# E_Key_BT.net
KiCad netlist of a schematic drawn in EAGLE
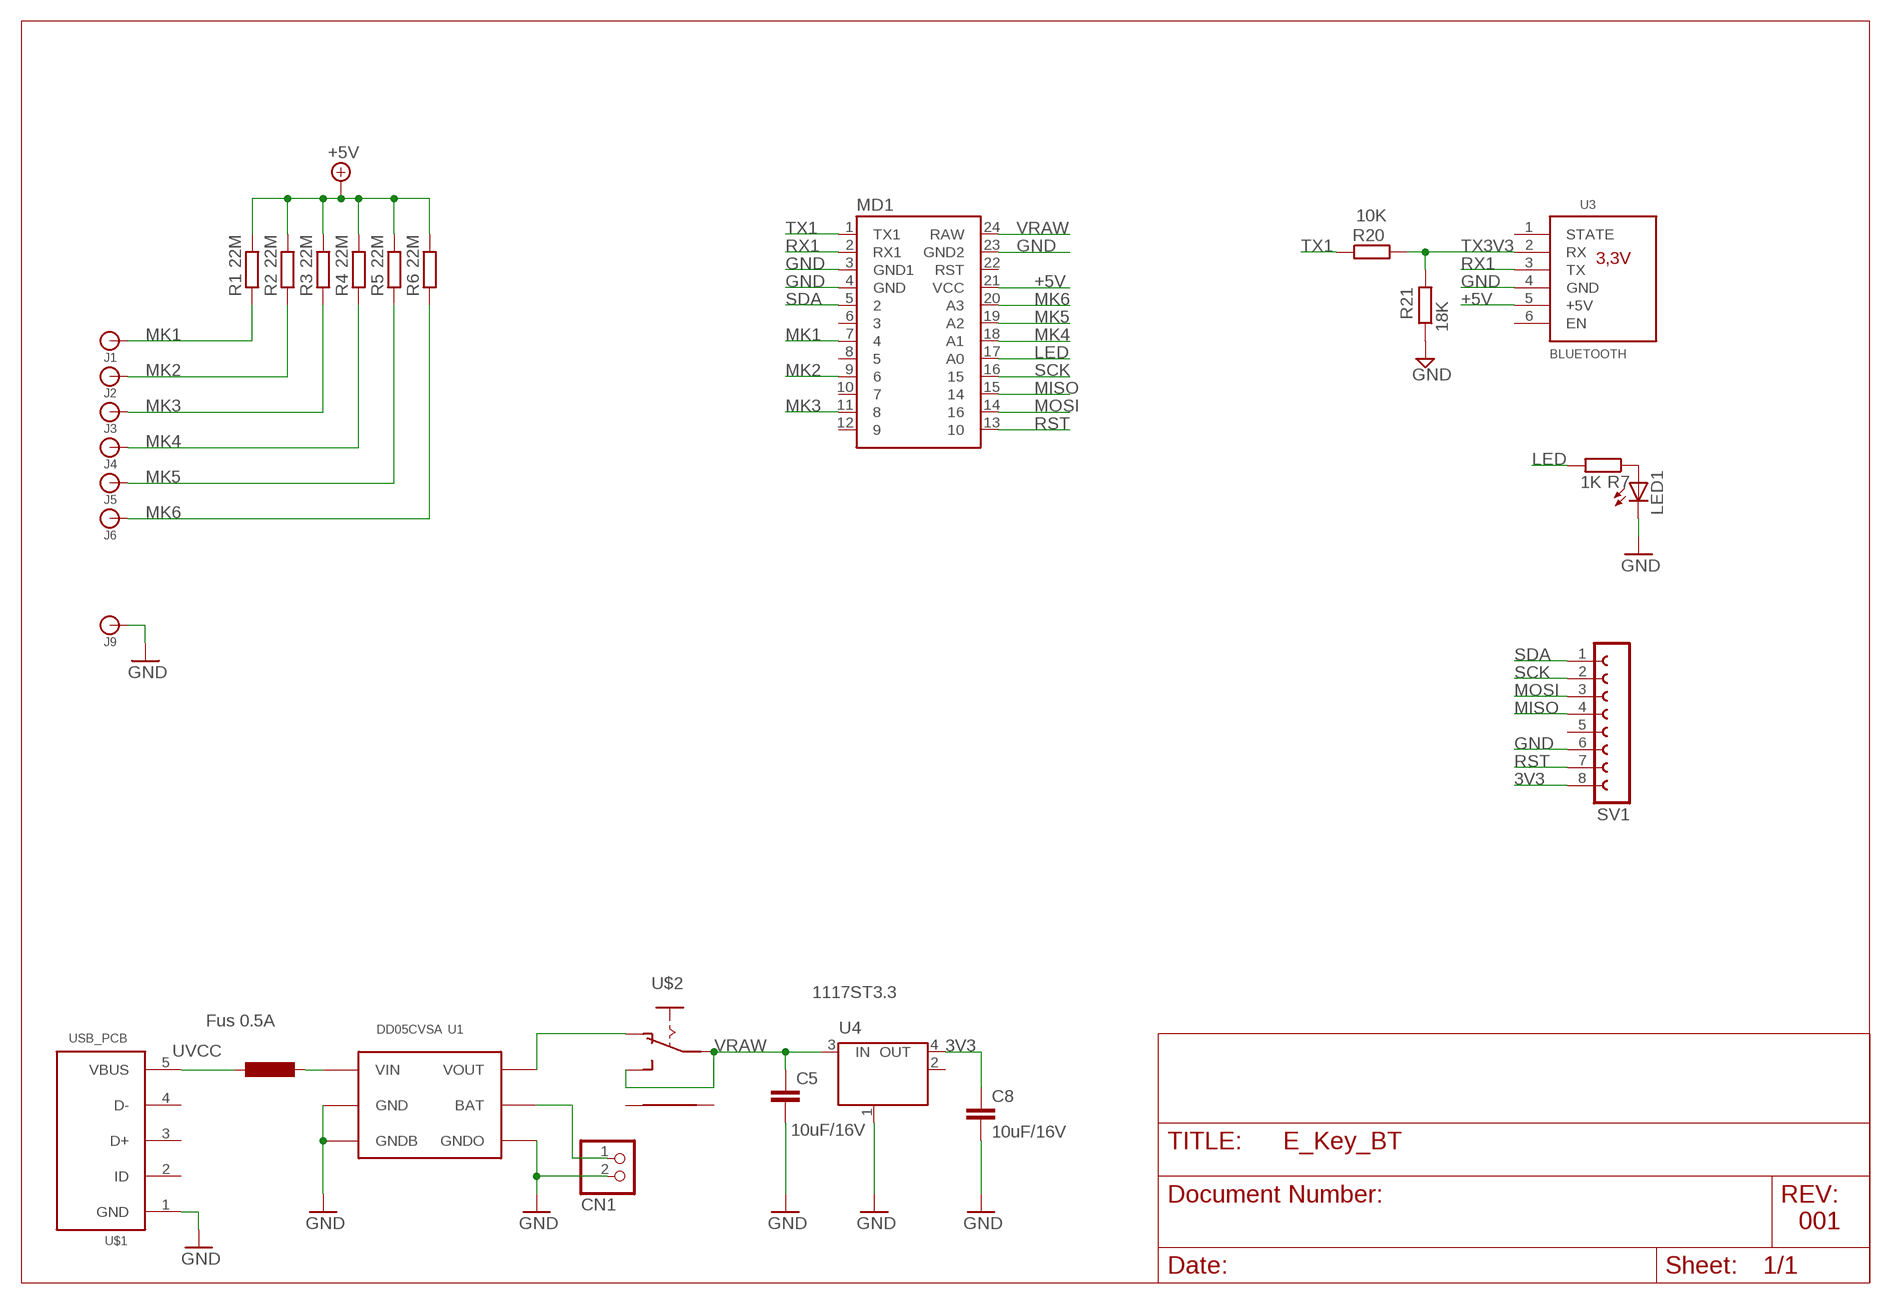
[diagram p0: schematic, sheet 1]

(export (version "E")
  (design (tool "Eeschema 10.0.6"))
  (components
    (comp (ref "C5")
      (value "10uF/16V")
      (footprint "eagle-import:C1206")
      (libsource (lib "eagle-import") (part "C-EUC1206"))
    )
    (comp (ref "C8")
      (value "10uF/16V")
      (footprint "eagle-import:C1206")
      (libsource (lib "eagle-import") (part "C-EUC1206"))
    )
    (comp (ref "CN1")
      (value "JST_2PIN-THM-RA")
      (footprint "eagle-import:JST-PH-2-THM-RA")
      (libsource (lib "eagle-import") (part "JST_2PIN-THM-RA"))
    )
    (comp (ref "F1")
      (value "Fus 0.5A")
      (footprint "eagle-import:R1206")
      (libsource (lib "eagle-import") (part "L-EU"))
    )
    (comp (ref "J1")
      (value "Hole")
      (footprint "eagle-import:BANANA_CONN")
      (libsource (lib "eagle-import") (part "BANANA_CONN"))
    )
    (comp (ref "J2")
      (value "Hole")
      (footprint "eagle-import:BANANA_CONN")
      (libsource (lib "eagle-import") (part "BANANA_CONN"))
    )
    (comp (ref "J3")
      (value "Hole")
      (footprint "eagle-import:BANANA_CONN")
      (libsource (lib "eagle-import") (part "BANANA_CONN"))
    )
    (comp (ref "J4")
      (value "Hole")
      (footprint "eagle-import:BANANA_CONN")
      (libsource (lib "eagle-import") (part "BANANA_CONN"))
    )
    (comp (ref "J5")
      (value "Hole")
      (footprint "eagle-import:BANANA_CONN")
      (libsource (lib "eagle-import") (part "BANANA_CONN"))
    )
    (comp (ref "J6")
      (value "Hole")
      (footprint "eagle-import:BANANA_CONN")
      (libsource (lib "eagle-import") (part "BANANA_CONN"))
    )
    (comp (ref "J9")
      (value "Hole")
      (footprint "eagle-import:BANANA_CONN")
      (libsource (lib "eagle-import") (part "BANANA_CONN"))
    )
    (comp (ref "LED1")
      (value "LED3MM")
      (footprint "eagle-import:LED3MM")
      (libsource (lib "eagle-import") (part "LED3MM"))
    )
    (comp (ref "MD1")
      (value "PRO_MICRO")
      (footprint "eagle-import:PRO_MICRO")
      (libsource (lib "eagle-import") (part "PRO_MICRO"))
    )
    (comp (ref "R1")
      (value "22M")
      (footprint "eagle-import:R0603")
      (libsource (lib "eagle-import") (part "R-EU_R0603"))
    )
    (comp (ref "R2")
      (value "22M")
      (footprint "eagle-import:R0603")
      (libsource (lib "eagle-import") (part "R-EU_R0603"))
    )
    (comp (ref "R3")
      (value "22M")
      (footprint "eagle-import:R0603")
      (libsource (lib "eagle-import") (part "R-EU_R0603"))
    )
    (comp (ref "R4")
      (value "22M")
      (footprint "eagle-import:R0603")
      (libsource (lib "eagle-import") (part "R-EU_R0603"))
    )
    (comp (ref "R5")
      (value "22M")
      (footprint "eagle-import:R0603")
      (libsource (lib "eagle-import") (part "R-EU_R0603"))
    )
    (comp (ref "R6")
      (value "22M")
      (footprint "eagle-import:R0603")
      (libsource (lib "eagle-import") (part "R-EU_R0603"))
    )
    (comp (ref "R7")
      (value "1K")
      (footprint "eagle-import:R0603")
      (libsource (lib "eagle-import") (part "R-EU_R0603"))
    )
    (comp (ref "R20")
      (value "10K")
      (footprint "eagle-import:R0603")
      (libsource (lib "eagle-import") (part "R-EU_R0603"))
    )
    (comp (ref "R21")
      (value "18K")
      (footprint "eagle-import:R0603")
      (libsource (lib "eagle-import") (part "R-EU_R0603"))
    )
    (comp (ref "SV1")
      (value "FE08-1")
      (footprint "eagle-import:FE08")
      (libsource (lib "eagle-import") (part "FE08-1"))
    )
    (comp (ref "U$1")
      (value "USB_PCB")
      (footprint "eagle-import:USB_PCB")
      (libsource (lib "eagle-import") (part "USB_PCB"))
    )
    (comp (ref "U$2")
      (value "ESCORNA_SK12F14D")
      (footprint "eagle-import:ESCORNA_SK-12D07")
      (libsource (lib "eagle-import") (part "ESCORNA_SK12F14D"))
    )
    (comp (ref "U1")
      (value "DD05CVSA")
      (footprint "eagle-import:DD05CVSA")
      (libsource (lib "eagle-import") (part "DD05CVSA"))
    )
    (comp (ref "U3")
      (value "BLUETOOTH")
      (footprint "eagle-import:BLUETOOTH_MODULE")
      (libsource (lib "eagle-import") (part "BLUETOOTH_MODULE"))
    )
    (comp (ref "U4")
      (value "1117ST3.3")
      (footprint "eagle-import:SOT223")
      (libsource (lib "eagle-import") (part "MC33269ST-3.3T3"))
    )
  )
  (nets
    (net (code "1") (name "+5V") (class "Default")
      (node (ref "MD1") (pin "21") (pinfunction "VCC_21") (pintype "bidirectional"))
      (node (ref "R1") (pin "2") (pinfunction "2_2") (pintype "passive"))
      (node (ref "R2") (pin "2") (pinfunction "2_2") (pintype "passive"))
      (node (ref "R3") (pin "2") (pinfunction "2_2") (pintype "passive"))
      (node (ref "R4") (pin "2") (pinfunction "2_2") (pintype "passive"))
      (node (ref "R5") (pin "2") (pinfunction "2_2") (pintype "passive"))
      (node (ref "R6") (pin "2") (pinfunction "2_2") (pintype "passive"))
      (node (ref "U3") (pin "5") (pinfunction "+5V_5") (pintype "bidirectional"))
    )
    (net (code "2") (name "/3V3") (class "Default")
      (node (ref "C8") (pin "1") (pinfunction "1_1") (pintype "passive"))
      (node (ref "SV1") (pin "8") (pinfunction "8_8") (pintype "passive"))
      (node (ref "U4") (pin "4") (pinfunction "OUT_4") (pintype "passive"))
    )
    (net (code "3") (name "/LED") (class "Default")
      (node (ref "MD1") (pin "17") (pinfunction "A0_17") (pintype "bidirectional"))
      (node (ref "R7") (pin "2") (pinfunction "2_2") (pintype "passive"))
    )
    (net (code "4") (name "/MISO") (class "Default")
      (node (ref "MD1") (pin "15") (pinfunction "14_15") (pintype "bidirectional"))
      (node (ref "SV1") (pin "4") (pinfunction "4_4") (pintype "passive"))
    )
    (net (code "5") (name "/MK1") (class "Default")
      (node (ref "J1") (pin "P$1") (pinfunction "1_P$1") (pintype "passive"))
      (node (ref "MD1") (pin "7") (pinfunction "4_7") (pintype "bidirectional"))
      (node (ref "R1") (pin "1") (pinfunction "1_1") (pintype "passive"))
    )
    (net (code "6") (name "/MK2") (class "Default")
      (node (ref "J2") (pin "P$1") (pinfunction "1_P$1") (pintype "passive"))
      (node (ref "MD1") (pin "9") (pinfunction "6_9") (pintype "bidirectional"))
      (node (ref "R2") (pin "1") (pinfunction "1_1") (pintype "passive"))
    )
    (net (code "7") (name "/MK3") (class "Default")
      (node (ref "J3") (pin "P$1") (pinfunction "1_P$1") (pintype "passive"))
      (node (ref "MD1") (pin "11") (pinfunction "8_11") (pintype "bidirectional"))
      (node (ref "R3") (pin "1") (pinfunction "1_1") (pintype "passive"))
    )
    (net (code "8") (name "/MK4") (class "Default")
      (node (ref "J4") (pin "P$1") (pinfunction "1_P$1") (pintype "passive"))
      (node (ref "MD1") (pin "18") (pinfunction "A1_18") (pintype "bidirectional"))
      (node (ref "R4") (pin "1") (pinfunction "1_1") (pintype "passive"))
    )
    (net (code "9") (name "/MK5") (class "Default")
      (node (ref "J5") (pin "P$1") (pinfunction "1_P$1") (pintype "passive"))
      (node (ref "MD1") (pin "19") (pinfunction "A2_19") (pintype "bidirectional"))
      (node (ref "R5") (pin "1") (pinfunction "1_1") (pintype "passive"))
    )
    (net (code "10") (name "/MK6") (class "Default")
      (node (ref "J6") (pin "P$1") (pinfunction "1_P$1") (pintype "passive"))
      (node (ref "MD1") (pin "20") (pinfunction "A3_20") (pintype "bidirectional"))
      (node (ref "R6") (pin "1") (pinfunction "1_1") (pintype "passive"))
    )
    (net (code "11") (name "/MOSI") (class "Default")
      (node (ref "MD1") (pin "14") (pinfunction "16_14") (pintype "bidirectional"))
      (node (ref "SV1") (pin "3") (pinfunction "3_3") (pintype "passive"))
    )
    (net (code "12") (name "/RST") (class "Default")
      (node (ref "MD1") (pin "13") (pinfunction "10_13") (pintype "bidirectional"))
      (node (ref "SV1") (pin "7") (pinfunction "7_7") (pintype "passive"))
    )
    (net (code "13") (name "/RX1") (class "Default")
      (node (ref "MD1") (pin "2") (pinfunction "RX1_2") (pintype "bidirectional"))
      (node (ref "U3") (pin "3") (pinfunction "TX_3") (pintype "bidirectional"))
    )
    (net (code "14") (name "/SCK") (class "Default")
      (node (ref "MD1") (pin "16") (pinfunction "15_16") (pintype "bidirectional"))
      (node (ref "SV1") (pin "2") (pinfunction "2_2") (pintype "passive"))
    )
    (net (code "15") (name "/SDA") (class "Default")
      (node (ref "MD1") (pin "5") (pinfunction "2_5") (pintype "bidirectional"))
      (node (ref "SV1") (pin "1") (pinfunction "1_1") (pintype "passive"))
    )
    (net (code "16") (name "/TX1") (class "Default")
      (node (ref "MD1") (pin "1") (pinfunction "TX1_1") (pintype "bidirectional"))
      (node (ref "R20") (pin "1") (pinfunction "1_1") (pintype "passive"))
    )
    (net (code "17") (name "/TX3V3") (class "Default")
      (node (ref "R20") (pin "2") (pinfunction "2_2") (pintype "passive"))
      (node (ref "R21") (pin "2") (pinfunction "2_2") (pintype "passive"))
      (node (ref "U3") (pin "2") (pinfunction "RX_2") (pintype "bidirectional"))
    )
    (net (code "18") (name "/UVCC") (class "Default")
      (node (ref "F1") (pin "2") (pinfunction "2_2") (pintype "passive"))
      (node (ref "U$1") (pin "5") (pinfunction "VBUS_5") (pintype "bidirectional"))
    )
    (net (code "19") (name "/VRAW") (class "Default")
      (node (ref "C5") (pin "1") (pinfunction "1_1") (pintype "passive"))
      (node (ref "MD1") (pin "24") (pinfunction "RAW_24") (pintype "bidirectional"))
      (node (ref "U$2") (pin "P$1") (pinfunction "P_P$1") (pintype "passive"))
      (node (ref "U$2") (pin "P$3") (pinfunction "S_P$3") (pintype "passive"))
      (node (ref "U4") (pin "3") (pinfunction "IN_3") (pintype "input"))
    )
    (net (code "20") (name "GND") (class "Default")
      (node (ref "C5") (pin "2") (pinfunction "2_2") (pintype "passive"))
      (node (ref "C8") (pin "2") (pinfunction "2_2") (pintype "passive"))
      (node (ref "CN1") (pin "2") (pinfunction "1_2") (pintype "passive"))
      (node (ref "J9") (pin "P$1") (pinfunction "1_P$1") (pintype "passive"))
      (node (ref "LED1") (pin "K") (pinfunction "C_K") (pintype "passive"))
      (node (ref "MD1") (pin "23") (pinfunction "GND2_23") (pintype "bidirectional"))
      (node (ref "MD1") (pin "3") (pinfunction "GND1_3") (pintype "bidirectional"))
      (node (ref "MD1") (pin "4") (pinfunction "GND_4") (pintype "bidirectional"))
      (node (ref "R21") (pin "1") (pinfunction "1_1") (pintype "passive"))
      (node (ref "SV1") (pin "6") (pinfunction "6_6") (pintype "passive"))
      (node (ref "U$1") (pin "1") (pinfunction "GND_1") (pintype "bidirectional"))
      (node (ref "U1") (pin "P$2") (pinfunction "GND_P$2") (pintype "bidirectional"))
      (node (ref "U1") (pin "P$4") (pinfunction "GNDB_P$4") (pintype "bidirectional"))
      (node (ref "U1") (pin "P$5") (pinfunction "GNDO_P$5") (pintype "bidirectional"))
      (node (ref "U3") (pin "4") (pinfunction "GND_4") (pintype "bidirectional"))
      (node (ref "U4") (pin "1") (pinfunction "GND/ADJ_1") (pintype "input"))
    )
    (net (code "21") (name "Net-(CN1-2)") (class "Default")
      (node (ref "CN1") (pin "1") (pinfunction "2_1") (pintype "passive"))
      (node (ref "U1") (pin "P$3") (pinfunction "BAT_P$3") (pintype "bidirectional"))
    )
    (net (code "22") (name "Net-(LED1-PadA)") (class "Default")
      (node (ref "LED1") (pin "A") (pinfunction "A_A") (pintype "passive"))
      (node (ref "R7") (pin "1") (pinfunction "1_1") (pintype "passive"))
    )
    (net (code "23") (name "Net-(U$2-O)") (class "Default")
      (node (ref "U$2") (pin "P$2") (pinfunction "O_P$2") (pintype "passive"))
      (node (ref "U1") (pin "P$6") (pinfunction "VOUT_P$6") (pintype "bidirectional"))
    )
    (net (code "24") (name "Net-(U1-VIN)") (class "Default")
      (node (ref "F1") (pin "1") (pinfunction "1_1") (pintype "passive"))
      (node (ref "U1") (pin "P$1") (pinfunction "VIN_P$1") (pintype "bidirectional"))
    )
    (net (code "25") (name "unconnected-(MD1-3-Pad6)") (class "Default")
      (node (ref "MD1") (pin "6") (pinfunction "3_6") (pintype "bidirectional"))
    )
    (net (code "26") (name "unconnected-(MD1-5-Pad8)") (class "Default")
      (node (ref "MD1") (pin "8") (pinfunction "5_8") (pintype "bidirectional"))
    )
    (net (code "27") (name "unconnected-(MD1-7-Pad10)") (class "Default")
      (node (ref "MD1") (pin "10") (pinfunction "7_10") (pintype "bidirectional"))
    )
    (net (code "28") (name "unconnected-(MD1-9-Pad12)") (class "Default")
      (node (ref "MD1") (pin "12") (pinfunction "9_12") (pintype "bidirectional"))
    )
    (net (code "29") (name "unconnected-(MD1-RST-Pad22)") (class "Default")
      (node (ref "MD1") (pin "22") (pinfunction "RST_22") (pintype "bidirectional"))
    )
    (net (code "30") (name "unconnected-(SV1-Pad5)") (class "Default")
      (node (ref "SV1") (pin "5") (pinfunction "5_5") (pintype "passive"))
    )
    (net (code "31") (name "unconnected-(U$1-D+-Pad3)") (class "Default")
      (node (ref "U$1") (pin "3") (pinfunction "D+_3") (pintype "bidirectional"))
    )
    (net (code "32") (name "unconnected-(U$1-D--Pad4)") (class "Default")
      (node (ref "U$1") (pin "4") (pinfunction "D-_4") (pintype "bidirectional"))
    )
    (net (code "33") (name "unconnected-(U$1-ID-Pad2)") (class "Default")
      (node (ref "U$1") (pin "2") (pinfunction "ID_2") (pintype "bidirectional"))
    )
    (net (code "34") (name "unconnected-(U$2-P$1-PadP$4)") (class "Default")
      (node (ref "U$2") (pin "P$4") (pinfunction "P$1_P$4") (pintype "passive"))
    )
    (net (code "35") (name "unconnected-(U$2-P$2-PadP$5)") (class "Default")
      (node (ref "U$2") (pin "P$5") (pinfunction "P$2_P$5") (pintype "bidirectional"))
    )
    (net (code "36") (name "unconnected-(U3-EN-Pad6)") (class "Default")
      (node (ref "U3") (pin "6") (pinfunction "EN_6") (pintype "bidirectional"))
    )
    (net (code "37") (name "unconnected-(U3-STATE-Pad1)") (class "Default")
      (node (ref "U3") (pin "1") (pinfunction "STATE_1") (pintype "bidirectional"))
    )
    (net (code "38") (name "unconnected-(U4-OUT-Pad2)") (class "Default")
      (node (ref "U4") (pin "2") (pinfunction "OUT_2") (pintype "passive"))
    )
  )
)
